# IR_Sensor.net
KiCad netlist of a schematic drawn in Altium Designer
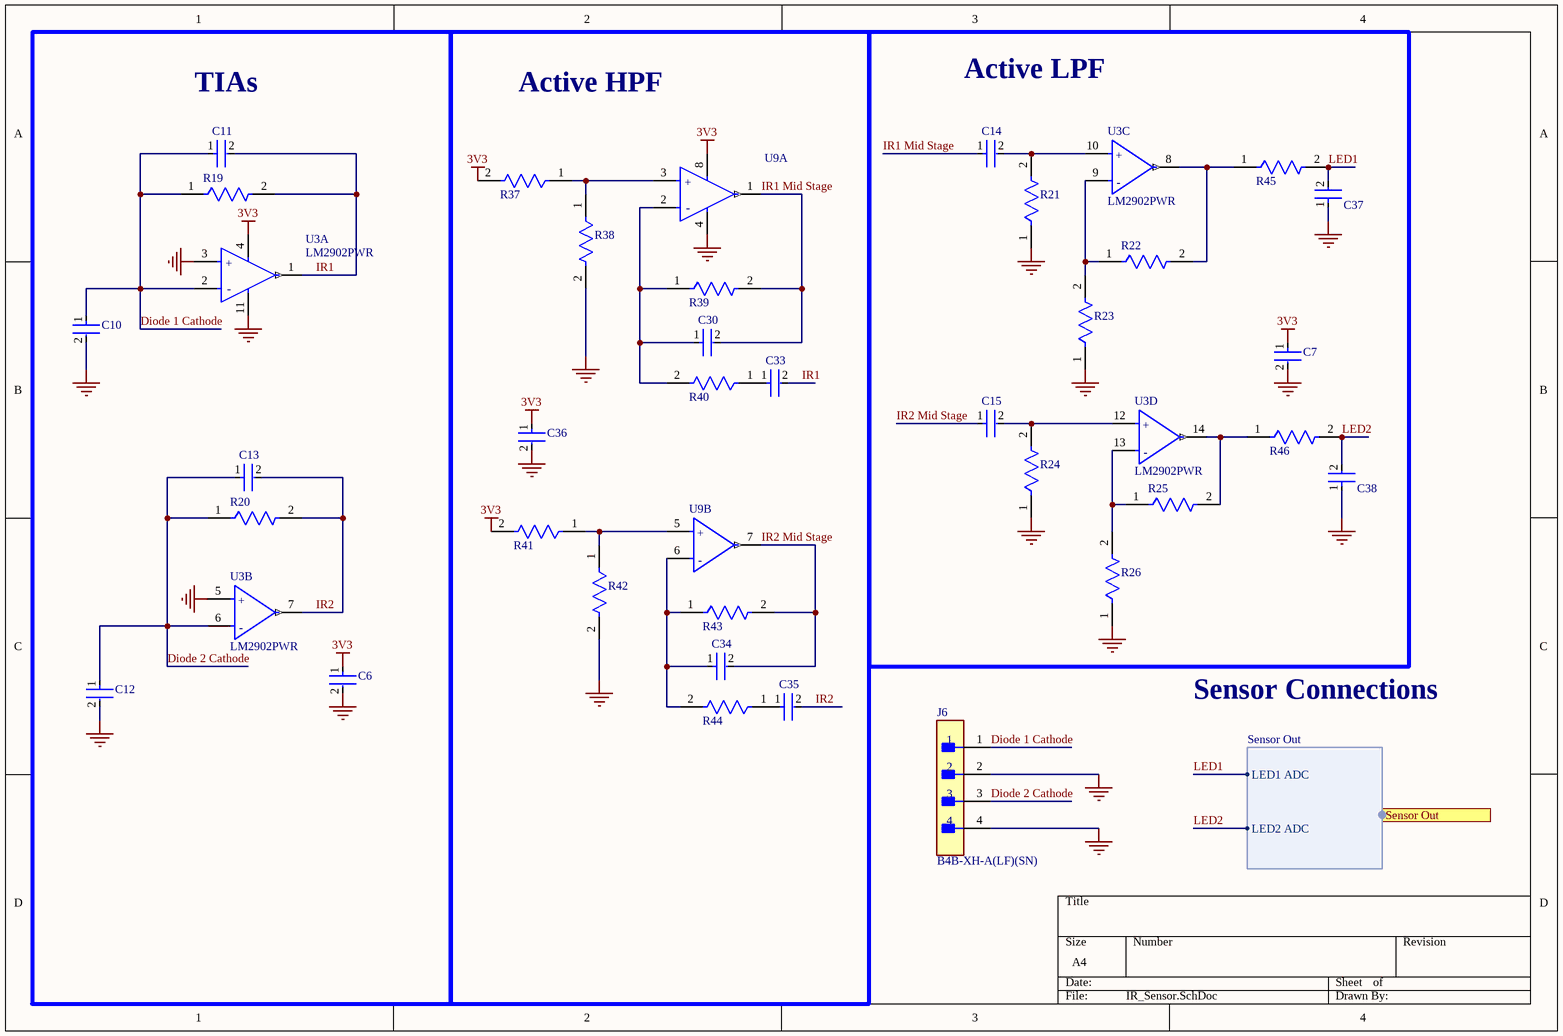
[diagram p0: IR_Sensor.SchDoc]

(export (version "E")
  (design (tool "Eeschema 10.0.6"))
  (components
    (comp (ref "C6")
      (value "LMK105B7104KVHF")
      (footprint "FP-0402-L_1_0_0_05-W_0_5-IPC_B")
      (description "None")
      (fields (field (name "TOLERANCE") "10%"))
      (libsource (lib "Altium Content Vault") (part "b4654b650e69147ec39a6b967a45e02"))
    )
    (comp (ref "C7")
      (value "LMK105B7104KVHF")
      (footprint "FP-0402-L_1_0_0_05-W_0_5-IPC_B")
      (description "None")
      (fields (field (name "TOLERANCE") "10%"))
      (libsource (lib "Altium Content Vault") (part "b4654b650e69147ec39a6b967a45e02"))
    )
    (comp (ref "C10")
      (value "GCM1555C1H4R0CA16D")
      (footprint "FP-GCM155-0_05-MFG")
      (description "Ceramic Capacitor for Automotive 4pF ±0.25pF 50VDC C0G 0402 Paper T/R")
      (libsource (lib "Altium Content Vault") (part "02cd4be3c70576c341d710602a673aa"))
    )
    (comp (ref "C11")
      (value "C0603C100D5GACAUTO")
      (footprint "FP-C0603C-CF-MFG")
      (description "C0603 10 pF C0G 30ppm/°C 0.5 pF 50 V")
      (fields
        (field (name "TOLERANCE") "0.5 pF")
        (field (name "OCTOPART") "https://octopart.com/c0603c100d5gacauto-kemet-81425946")
      )
      (libsource (lib "Altium Content Vault") (part "b4654b650e69147ec39a6b967a45e02"))
    )
    (comp (ref "C12")
      (value "GCM1555C1H4R0CA16D")
      (footprint "FP-GCM155-0_05-MFG")
      (description "Ceramic Capacitor for Automotive 4pF ±0.25pF 50VDC C0G 0402 Paper T/R")
      (libsource (lib "Altium Content Vault") (part "02cd4be3c70576c341d710602a673aa"))
    )
    (comp (ref "C13")
      (value "C0603C100D5GACAUTO")
      (footprint "FP-C0603C-CF-MFG")
      (description "C0603 10 pF C0G 30ppm/°C 0.5 pF 50 V")
      (fields
        (field (name "TOLERANCE") "0.5 pF")
        (field (name "OCTOPART") "https://octopart.com/c0603c100d5gacauto-kemet-81425946")
      )
      (libsource (lib "Altium Content Vault") (part "b4654b650e69147ec39a6b967a45e02"))
    )
    (comp (ref "C14")
      (value "C0603C104K3RACTU")
      (footprint "FP-C0603C-CF-MFG")
      (description "CAP CER 0.1UF 25V X7R 0603")
      (fields
        (field (name "OCTOPART") "https://octopart.com/c0603c104k3ractu-kemet-127541")
        (field (name "MANUFACTURER") "KEMET")
      )
      (libsource (lib "Altium Content Vault") (part "b4654b650e69147ec39a6b967a45e02"))
    )
    (comp (ref "C15")
      (value "C0603C104K3RACTU")
      (footprint "FP-C0603C-CF-MFG")
      (description "CAP CER 0.1UF 25V X7R 0603")
      (fields
        (field (name "OCTOPART") "https://octopart.com/c0603c104k3ractu-kemet-127541")
        (field (name "MANUFACTURER") "KEMET")
      )
      (libsource (lib "Altium Content Vault") (part "b4654b650e69147ec39a6b967a45e02"))
    )
    (comp (ref "C30")
      (value "C0603C100D5GACAUTO")
      (footprint "FP-C0603C-CF-MFG")
      (description "C0603 10 pF C0G 30ppm/°C 0.5 pF 50 V")
      (fields
        (field (name "TOLERANCE") "0.5 pF")
        (field (name "OCTOPART") "https://octopart.com/c0603c100d5gacauto-kemet-81425946")
      )
      (libsource (lib "Altium Content Vault") (part "b4654b650e69147ec39a6b967a45e02"))
    )
    (comp (ref "C33")
      (value "C0603C104K3RACTU")
      (footprint "FP-C0603C-CF-MFG")
      (description "CAP CER 0.1UF 25V X7R 0603")
      (fields
        (field (name "OCTOPART") "https://octopart.com/c0603c104k3ractu-kemet-127541")
        (field (name "MANUFACTURER") "KEMET")
      )
      (libsource (lib "Altium Content Vault") (part "b4654b650e69147ec39a6b967a45e02"))
    )
    (comp (ref "C34")
      (value "C0603C100D5GACAUTO")
      (footprint "FP-C0603C-CF-MFG")
      (description "C0603 10 pF C0G 30ppm/°C 0.5 pF 50 V")
      (fields
        (field (name "TOLERANCE") "0.5 pF")
        (field (name "OCTOPART") "https://octopart.com/c0603c100d5gacauto-kemet-81425946")
      )
      (libsource (lib "Altium Content Vault") (part "b4654b650e69147ec39a6b967a45e02"))
    )
    (comp (ref "C35")
      (value "C0603C104K3RACTU")
      (footprint "FP-C0603C-CF-MFG")
      (description "CAP CER 0.1UF 25V X7R 0603")
      (fields
        (field (name "OCTOPART") "https://octopart.com/c0603c104k3ractu-kemet-127541")
        (field (name "MANUFACTURER") "KEMET")
      )
      (libsource (lib "Altium Content Vault") (part "b4654b650e69147ec39a6b967a45e02"))
    )
    (comp (ref "C36")
      (value "LMK105B7104KVHF")
      (footprint "FP-0402-L_1_0_0_05-W_0_5-IPC_B")
      (description "None")
      (fields (field (name "TOLERANCE") "10%"))
      (libsource (lib "Altium Content Vault") (part "b4654b650e69147ec39a6b967a45e02"))
    )
    (comp (ref "C37")
      (value "C0603C104K3RACTU")
      (footprint "FP-C0603C-CF-MFG")
      (description "CAP CER 0.1UF 25V X7R 0603")
      (fields
        (field (name "OCTOPART") "https://octopart.com/c0603c104k3ractu-kemet-127541")
        (field (name "MANUFACTURER") "KEMET")
      )
      (libsource (lib "Altium Content Vault") (part "b4654b650e69147ec39a6b967a45e02"))
    )
    (comp (ref "C38")
      (value "C0603C104K3RACTU")
      (footprint "FP-C0603C-CF-MFG")
      (description "CAP CER 0.1UF 25V X7R 0603")
      (fields
        (field (name "OCTOPART") "https://octopart.com/c0603c104k3ractu-kemet-127541")
        (field (name "MANUFACTURER") "KEMET")
      )
      (libsource (lib "Altium Content Vault") (part "b4654b650e69147ec39a6b967a45e02"))
    )
    (comp (ref "J6")
      (value "B4B-XH-A(LF)(SN)")
      (footprint "FP-B4B-XH-A_LF_SN-MFG")
      (description "CONN HEADER VERT 4POS 2.5MM")
      (libsource (lib "Altium Content Vault") (part "299a8cea1bdcbc3624fe62c390fa72c"))
    )
    (comp (ref "R19")
      (value "MCT0603MD1002DP500")
      (footprint "FP-MCT0603-IPC_A")
      (description "RES SMD 100 OHM 1% 1/8W 0603")
      (fields (field (name "TOLERANCE") "0.5%"))
      (libsource (lib "Altium Content Vault") (part "1029c3af85768c4190bb7ad29bc67b5"))
    )
    (comp (ref "R20")
      (value "MCT0603MD1002DP500")
      (footprint "FP-MCT0603-IPC_A")
      (description "RES SMD 100 OHM 1% 1/8W 0603")
      (fields (field (name "TOLERANCE") "0.5%"))
      (libsource (lib "Altium Content Vault") (part "1029c3af85768c4190bb7ad29bc67b5"))
    )
    (comp (ref "R21")
      (value "AC0603JR-0747KL")
      (footprint "FP-AC0603-IPC_A")
      (description "RES 47kΩ 5.00% 0.1W 0603")
      (fields (field (name "TOLERANCE") "5%"))
      (libsource (lib "Altium Content Vault") (part "1029c3af85768c4190bb7ad29bc67b5"))
    )
    (comp (ref "R22")
      (value "RT0603DRE073K3L")
      (footprint "FP-RT0603-MFG")
      (description "RES 3.30K OHM 1/10W .5% SMD 0603")
      (fields
        (field (name "MANUFACTURER") "Yageo")
        (field (name "OCTOPART") "https://octopart.com/rt0603dre073k3l-yageo-1479702")
      )
      (libsource (lib "Altium Content Vault") (part "1029c3af85768c4190bb7ad29bc67b5"))
    )
    (comp (ref "R23")
      (value "AT0603BRD071KL")
      (footprint "FP-AT0603-IPC_A")
      (description "Thin Film Chip Resistors Automotive Grade 1kΩ 0.1% 25ppm/°C 0603")
      (fields (field (name "TOLERANCE") "0.1%"))
      (libsource (lib "Altium Content Vault") (part "1029c3af85768c4190bb7ad29bc67b5"))
    )
    (comp (ref "R24")
      (value "AC0603JR-0747KL")
      (footprint "FP-AC0603-IPC_A")
      (description "RES 47kΩ 5.00% 0.1W 0603")
      (fields (field (name "TOLERANCE") "5%"))
      (libsource (lib "Altium Content Vault") (part "1029c3af85768c4190bb7ad29bc67b5"))
    )
    (comp (ref "R25")
      (value "RT0603DRE073K3L")
      (footprint "FP-RT0603-MFG")
      (description "RES 3.30K OHM 1/10W .5% SMD 0603")
      (fields
        (field (name "MANUFACTURER") "Yageo")
        (field (name "OCTOPART") "https://octopart.com/rt0603dre073k3l-yageo-1479702")
      )
      (libsource (lib "Altium Content Vault") (part "1029c3af85768c4190bb7ad29bc67b5"))
    )
    (comp (ref "R26")
      (value "AT0603BRD071KL")
      (footprint "FP-AT0603-IPC_A")
      (description "Thin Film Chip Resistors Automotive Grade 1kΩ 0.1% 25ppm/°C 0603")
      (fields (field (name "TOLERANCE") "0.1%"))
      (libsource (lib "Altium Content Vault") (part "1029c3af85768c4190bb7ad29bc67b5"))
    )
    (comp (ref "R37")
      (value "CRCW0603100KFKEI")
      (footprint "FP-CRCW0603-e3-MFG")
      (description "RES Thick Film, 100kΩ, 1%, 0.1W, 100ppm/°C, 0603")
      (fields (field (name "TOLERANCE") "1%"))
      (libsource (lib "Altium Content Vault") (part "1029c3af85768c4190bb7ad29bc67b5"))
    )
    (comp (ref "R38")
      (value "CRCW0603100KFKEI")
      (footprint "FP-CRCW0603-e3-MFG")
      (description "RES Thick Film, 100kΩ, 1%, 0.1W, 100ppm/°C, 0603")
      (fields (field (name "TOLERANCE") "1%"))
      (libsource (lib "Altium Content Vault") (part "1029c3af85768c4190bb7ad29bc67b5"))
    )
    (comp (ref "R39")
      (value "CRCW0603100KFKEI")
      (footprint "FP-CRCW0603-e3-MFG")
      (description "RES Thick Film, 100kΩ, 1%, 0.1W, 100ppm/°C, 0603")
      (fields (field (name "TOLERANCE") "1%"))
      (libsource (lib "Altium Content Vault") (part "1029c3af85768c4190bb7ad29bc67b5"))
    )
    (comp (ref "R40")
      (value "AC0603JR-7W10KL")
      (footprint "FP-AC0603-IPC_A")
      (description "RES 10kΩ 5.00% 0.2W 0603")
      (libsource (lib "Altium Content Vault") (part "1029c3af85768c4190bb7ad29bc67b5"))
    )
    (comp (ref "R41")
      (value "CRCW0603100KFKEI")
      (footprint "FP-CRCW0603-e3-MFG")
      (description "RES Thick Film, 100kΩ, 1%, 0.1W, 100ppm/°C, 0603")
      (fields (field (name "TOLERANCE") "1%"))
      (libsource (lib "Altium Content Vault") (part "1029c3af85768c4190bb7ad29bc67b5"))
    )
    (comp (ref "R42")
      (value "CRCW0603100KFKEI")
      (footprint "FP-CRCW0603-e3-MFG")
      (description "RES Thick Film, 100kΩ, 1%, 0.1W, 100ppm/°C, 0603")
      (fields (field (name "TOLERANCE") "1%"))
      (libsource (lib "Altium Content Vault") (part "1029c3af85768c4190bb7ad29bc67b5"))
    )
    (comp (ref "R43")
      (value "CRCW0603100KFKEI")
      (footprint "FP-CRCW0603-e3-MFG")
      (description "RES Thick Film, 100kΩ, 1%, 0.1W, 100ppm/°C, 0603")
      (fields (field (name "TOLERANCE") "1%"))
      (libsource (lib "Altium Content Vault") (part "1029c3af85768c4190bb7ad29bc67b5"))
    )
    (comp (ref "R44")
      (value "AC0603JR-7W10KL")
      (footprint "FP-AC0603-IPC_A")
      (description "RES 10kΩ 5.00% 0.2W 0603")
      (libsource (lib "Altium Content Vault") (part "1029c3af85768c4190bb7ad29bc67b5"))
    )
    (comp (ref "R45")
      (value "CRCW0603100KFKEI")
      (footprint "FP-CRCW0603-e3-MFG")
      (description "RES Thick Film, 100kΩ, 1%, 0.1W, 100ppm/°C, 0603")
      (fields (field (name "TOLERANCE") "1%"))
      (libsource (lib "Altium Content Vault") (part "1029c3af85768c4190bb7ad29bc67b5"))
    )
    (comp (ref "R46")
      (value "CRCW0603100KFKEI")
      (footprint "FP-CRCW0603-e3-MFG")
      (description "RES Thick Film, 100kΩ, 1%, 0.1W, 100ppm/°C, 0603")
      (fields (field (name "TOLERANCE") "1%"))
      (libsource (lib "Altium Content Vault") (part "1029c3af85768c4190bb7ad29bc67b5"))
    )
    (comp (ref "U3")
      (value "LM2902PWR")
      (footprint "FP-PW0014A-IPC_C")
      (description "IC OPAMP GP 4 CIRCUIT 14TSSOP")
      (libsource (lib "Altium Content Vault") (part "d04e61c43a6e83883993e7b996e8d67"))
    )
    (comp (ref "U9")
      (value "LMV358AIDR")
      (footprint "FP-D0008A-IPC_C")
      (description "IC OPAMP GP 2 CIRCUIT 8SOIC")
      (libsource (lib "Altium Content Vault") (part "499df5fc91ff7ad023bcaf249d8becd"))
    )
  )
  (nets
    (net (code "3") (name "/Diode 1 Cathode") (class "Default")
      (node (ref "C10") (pin "1") (pinfunction "1_1") (pintype "passive"))
      (node (ref "C11") (pin "1") (pinfunction "1_1") (pintype "passive"))
      (node (ref "J6") (pin "1") (pinfunction "1_1") (pintype "passive"))
      (node (ref "R19") (pin "1") (pinfunction "1_1") (pintype "passive"))
      (node (ref "U3") (pin "2") (pinfunction "1IN-_2") (pintype "tri_state"))
    )
    (net (code "4") (name "/Diode 2 Cathode") (class "Default")
      (node (ref "C12") (pin "1") (pinfunction "1_1") (pintype "passive"))
      (node (ref "C13") (pin "1") (pinfunction "1_1") (pintype "passive"))
      (node (ref "J6") (pin "3") (pinfunction "3_3") (pintype "passive"))
      (node (ref "R20") (pin "1") (pinfunction "1_1") (pintype "passive"))
      (node (ref "U3") (pin "6") (pinfunction "2IN-_6") (pintype "tri_state"))
    )
    (net (code "5") (name "/IR1") (class "Default")
      (node (ref "C11") (pin "2") (pinfunction "2_2") (pintype "passive"))
      (node (ref "C33") (pin "2") (pinfunction "2_2") (pintype "passive"))
      (node (ref "R19") (pin "2") (pinfunction "2_2") (pintype "passive"))
      (node (ref "U3") (pin "1") (pinfunction "1OUT_1") (pintype "output"))
    )
    (net (code "6") (name "/IR1 Mid Stage") (class "Default")
      (node (ref "C14") (pin "1") (pinfunction "1_1") (pintype "passive"))
      (node (ref "C30") (pin "2") (pinfunction "2_2") (pintype "passive"))
      (node (ref "R39") (pin "2") (pinfunction "2_2") (pintype "passive"))
      (node (ref "U9") (pin "1") (pinfunction "OUT_A_1") (pintype "output"))
    )
    (net (code "7") (name "/IR2") (class "Default")
      (node (ref "C13") (pin "2") (pinfunction "2_2") (pintype "passive"))
      (node (ref "C35") (pin "2") (pinfunction "2_2") (pintype "passive"))
      (node (ref "R20") (pin "2") (pinfunction "2_2") (pintype "passive"))
      (node (ref "U3") (pin "7") (pinfunction "2OUT_7") (pintype "output"))
    )
    (net (code "8") (name "/IR2 Mid Stage") (class "Default")
      (node (ref "C15") (pin "1") (pinfunction "1_1") (pintype "passive"))
      (node (ref "C34") (pin "2") (pinfunction "2_2") (pintype "passive"))
      (node (ref "R43") (pin "2") (pinfunction "2_2") (pintype "passive"))
      (node (ref "U9") (pin "7") (pinfunction "OUT_B_7") (pintype "output"))
    )
    (net (code "9") (name "/LED1") (class "Default")
      (node (ref "C37") (pin "2") (pinfunction "2_2") (pintype "passive"))
      (node (ref "R45") (pin "2") (pinfunction "2_2") (pintype "passive"))
    )
    (net (code "10") (name "/LED2") (class "Default")
      (node (ref "C38") (pin "2") (pinfunction "2_2") (pintype "passive"))
      (node (ref "R46") (pin "2") (pinfunction "2_2") (pintype "passive"))
    )
    (net (code "12") (name "3V3") (class "Default")
      (node (ref "C36") (pin "1") (pinfunction "1_1") (pintype "passive"))
      (node (ref "C6") (pin "1") (pinfunction "1_1") (pintype "passive"))
      (node (ref "C7") (pin "1") (pinfunction "1_1") (pintype "passive"))
      (node (ref "R37") (pin "2") (pinfunction "2_2") (pintype "passive"))
      (node (ref "R41") (pin "2") (pinfunction "2_2") (pintype "passive"))
      (node (ref "U3") (pin "4") (pinfunction "VCC_4") (pintype "power_in"))
      (node (ref "U9") (pin "8") (pinfunction "V+_8") (pintype "power_in"))
    )
    (net (code "13") (name "GND") (class "Default")
      (node (ref "C10") (pin "2") (pinfunction "2_2") (pintype "passive"))
      (node (ref "C12") (pin "2") (pinfunction "2_2") (pintype "passive"))
      (node (ref "C36") (pin "2") (pinfunction "2_2") (pintype "passive"))
      (node (ref "C37") (pin "1") (pinfunction "1_1") (pintype "passive"))
      (node (ref "C38") (pin "1") (pinfunction "1_1") (pintype "passive"))
      (node (ref "C6") (pin "2") (pinfunction "2_2") (pintype "passive"))
      (node (ref "C7") (pin "2") (pinfunction "2_2") (pintype "passive"))
      (node (ref "J6") (pin "2") (pinfunction "2_2") (pintype "passive"))
      (node (ref "J6") (pin "4") (pinfunction "4_4") (pintype "passive"))
      (node (ref "R21") (pin "1") (pinfunction "1_1") (pintype "passive"))
      (node (ref "R23") (pin "1") (pinfunction "1_1") (pintype "passive"))
      (node (ref "R24") (pin "1") (pinfunction "1_1") (pintype "passive"))
      (node (ref "R26") (pin "1") (pinfunction "1_1") (pintype "passive"))
      (node (ref "R38") (pin "2") (pinfunction "2_2") (pintype "passive"))
      (node (ref "R42") (pin "2") (pinfunction "2_2") (pintype "passive"))
      (node (ref "U3") (pin "11") (pinfunction "GND_11") (pintype "power_in"))
      (node (ref "U3") (pin "3") (pinfunction "1IN+_3") (pintype "tri_state"))
      (node (ref "U3") (pin "5") (pinfunction "2IN+_5") (pintype "tri_state"))
      (node (ref "U9") (pin "4") (pinfunction "V-_4") (pintype "power_in"))
    )
    (net (code "14") (name "Net-(C33-Pad1)") (class "Default")
      (node (ref "C33") (pin "1") (pinfunction "1_1") (pintype "passive"))
      (node (ref "R40") (pin "1") (pinfunction "1_1") (pintype "passive"))
    )
    (net (code "15") (name "Net-(C35-Pad1)") (class "Default")
      (node (ref "C35") (pin "1") (pinfunction "1_1") (pintype "passive"))
      (node (ref "R44") (pin "1") (pinfunction "1_1") (pintype "passive"))
    )
    (net (code "16") (name "Net-(U3C-3IN+)") (class "Default")
      (node (ref "C14") (pin "2") (pinfunction "2_2") (pintype "passive"))
      (node (ref "R21") (pin "2") (pinfunction "2_2") (pintype "passive"))
      (node (ref "U3") (pin "10") (pinfunction "3IN+_10") (pintype "tri_state"))
    )
    (net (code "17") (name "Net-(U3C-3IN-)") (class "Default")
      (node (ref "R22") (pin "1") (pinfunction "1_1") (pintype "passive"))
      (node (ref "R23") (pin "2") (pinfunction "2_2") (pintype "passive"))
      (node (ref "U3") (pin "9") (pinfunction "3IN-_9") (pintype "tri_state"))
    )
    (net (code "18") (name "Net-(U3C-3OUT)") (class "Default")
      (node (ref "R22") (pin "2") (pinfunction "2_2") (pintype "passive"))
      (node (ref "R45") (pin "1") (pinfunction "1_1") (pintype "passive"))
      (node (ref "U3") (pin "8") (pinfunction "3OUT_8") (pintype "output"))
    )
    (net (code "19") (name "Net-(U3D-4IN+)") (class "Default")
      (node (ref "C15") (pin "2") (pinfunction "2_2") (pintype "passive"))
      (node (ref "R24") (pin "2") (pinfunction "2_2") (pintype "passive"))
      (node (ref "U3") (pin "12") (pinfunction "4IN+_12") (pintype "tri_state"))
    )
    (net (code "20") (name "Net-(U3D-4IN-)") (class "Default")
      (node (ref "R25") (pin "1") (pinfunction "1_1") (pintype "passive"))
      (node (ref "R26") (pin "2") (pinfunction "2_2") (pintype "passive"))
      (node (ref "U3") (pin "13") (pinfunction "4IN-_13") (pintype "tri_state"))
    )
    (net (code "21") (name "Net-(U3D-4OUT)") (class "Default")
      (node (ref "R25") (pin "2") (pinfunction "2_2") (pintype "passive"))
      (node (ref "R46") (pin "1") (pinfunction "1_1") (pintype "passive"))
      (node (ref "U3") (pin "14") (pinfunction "4OUT_14") (pintype "output"))
    )
    (net (code "22") (name "Net-(U9A-+IN_A)") (class "Default")
      (node (ref "R37") (pin "1") (pinfunction "1_1") (pintype "passive"))
      (node (ref "R38") (pin "1") (pinfunction "1_1") (pintype "passive"))
      (node (ref "U9") (pin "3") (pinfunction "+IN_A_3") (pintype "tri_state"))
    )
    (net (code "23") (name "Net-(U9A--IN_A)") (class "Default")
      (node (ref "C30") (pin "1") (pinfunction "1_1") (pintype "passive"))
      (node (ref "R39") (pin "1") (pinfunction "1_1") (pintype "passive"))
      (node (ref "R40") (pin "2") (pinfunction "2_2") (pintype "passive"))
      (node (ref "U9") (pin "2") (pinfunction "-IN_A_2") (pintype "tri_state"))
    )
    (net (code "24") (name "Net-(U9B-+IN_B)") (class "Default")
      (node (ref "R41") (pin "1") (pinfunction "1_1") (pintype "passive"))
      (node (ref "R42") (pin "1") (pinfunction "1_1") (pintype "passive"))
      (node (ref "U9") (pin "5") (pinfunction "+IN_B_5") (pintype "tri_state"))
    )
    (net (code "25") (name "Net-(U9B--IN_B)") (class "Default")
      (node (ref "C34") (pin "1") (pinfunction "1_1") (pintype "passive"))
      (node (ref "R43") (pin "1") (pinfunction "1_1") (pintype "passive"))
      (node (ref "R44") (pin "2") (pinfunction "2_2") (pintype "passive"))
      (node (ref "U9") (pin "6") (pinfunction "-IN_B_6") (pintype "tri_state"))
    )
  )
)
